# reg_bats.net
KiCad netlist of a schematic drawn in Altium Designer
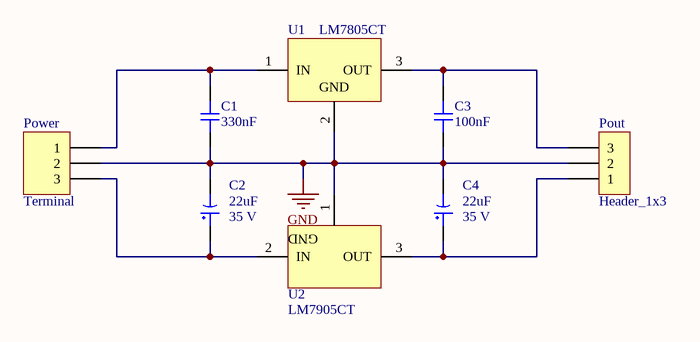
[diagram p0: reg_bats.SchDoc]

(export (version "E")
  (design (tool "Eeschema 10.0.6"))
  (components
    (comp (ref "C1")
      (value "330nF")
      (footprint "C400-550-150")
      (description "Capacitor")
      (fields (field (name "VOLTAGE") "100 V") (field (name "PUBLISHER") "Altium Limited"))
      (libsource (lib "GPDSE") (part "Capacitor"))
    )
    (comp (ref "C2")
      (value "22uF")
      (footprint "CP-RAD-4.0mm-7.0mm-1.5mm")
      (description "Electrolytic Capacitor")
      (fields (field (name "VOLTAGE") "35 V"))
      (libsource (lib "GPDSE") (part "Capacitor-Electrolytic"))
    )
    (comp (ref "C3")
      (value "100nF")
      (footprint "C200-350-150")
      (description "Capacitor")
      (fields (field (name "VOLTAGE") "100 V") (field (name "PUBLISHER") "Altium Limited"))
      (libsource (lib "GPDSE") (part "Capacitor"))
    )
    (comp (ref "C4")
      (value "22uF")
      (footprint "CP-RAD-4.0mm-7.0mm-1.5mm")
      (description "Electrolytic Capacitor")
      (fields (field (name "VOLTAGE") "35 V"))
      (libsource (lib "GPDSE") (part "Capacitor-Electrolytic"))
    )
    (comp (ref "Pout")
      (value "Header_1x3")
      (footprint "HDR-M-1x3-2.54mm-180-9.2mm")
      (description "Header, 1 Line, 3 Columns, 3 Pins")
      (fields (field (name "PUBLISHER") "Altium Limited"))
      (libsource (lib "GPDSE") (part "Header_1x3"))
    )
    (comp (ref "Power")
      (value "Terminal")
      (footprint "KRE_3")
      (description "Terminal Block 1x3")
      (libsource (lib "GPDSE") (part "KRE_3"))
    )
    (comp (ref "U1")
      (value "LM7805CT")
      (footprint "TO-220/123")
      (description "3-Terminal 1 A Positive 5 V Voltage Regulator")
      (libsource (lib "GPDSE") (part "LM7805CT"))
    )
    (comp (ref "U2")
      (value "LM7905CT")
      (footprint "TO-220/123")
      (description "3-Terminal 1 A Negative 5 V Voltage Regulator")
      (libsource (lib "GPDSE") (part "LM7905CT"))
    )
  )
  (nets
    (net (code "1") (name "GND") (class "Default")
      (node (ref "C1") (pin "1") (pinfunction "1_1") (pintype "passive"))
      (node (ref "C2") (pin "2") (pinfunction "2_2") (pintype "passive"))
      (node (ref "C3") (pin "1") (pinfunction "1_1") (pintype "passive"))
      (node (ref "C4") (pin "2") (pinfunction "2_2") (pintype "passive"))
      (node (ref "Pout") (pin "2") (pinfunction "2_2") (pintype "passive"))
      (node (ref "Power") (pin "2") (pinfunction "2_2") (pintype "passive"))
      (node (ref "U1") (pin "2") (pinfunction "GND_2") (pintype "passive"))
      (node (ref "U2") (pin "1") (pinfunction "GND_1") (pintype "passive"))
    )
    (net (code "2") (name "Net-(U1-IN)") (class "Default")
      (node (ref "C1") (pin "2") (pinfunction "2_2") (pintype "passive"))
      (node (ref "Power") (pin "1") (pinfunction "1_1") (pintype "passive"))
      (node (ref "U1") (pin "1") (pinfunction "IN_1") (pintype "passive"))
    )
    (net (code "3") (name "Net-(U1-OUT)") (class "Default")
      (node (ref "C3") (pin "2") (pinfunction "2_2") (pintype "passive"))
      (node (ref "Pout") (pin "3") (pinfunction "3_3") (pintype "passive"))
      (node (ref "U1") (pin "3") (pinfunction "OUT_3") (pintype "passive"))
    )
    (net (code "4") (name "Net-(U2-IN)") (class "Default")
      (node (ref "C2") (pin "1") (pinfunction "1_1") (pintype "passive"))
      (node (ref "Power") (pin "3") (pinfunction "3_3") (pintype "passive"))
      (node (ref "U2") (pin "2") (pinfunction "IN_2") (pintype "passive"))
    )
    (net (code "5") (name "Net-(U2-OUT)") (class "Default")
      (node (ref "C4") (pin "1") (pinfunction "1_1") (pintype "passive"))
      (node (ref "Pout") (pin "1") (pinfunction "1_1") (pintype "passive"))
      (node (ref "U2") (pin "3") (pinfunction "OUT_3") (pintype "passive"))
    )
  )
)
